# MCU_CAN.net
KiCad netlist of a schematic drawn in Altium Designer
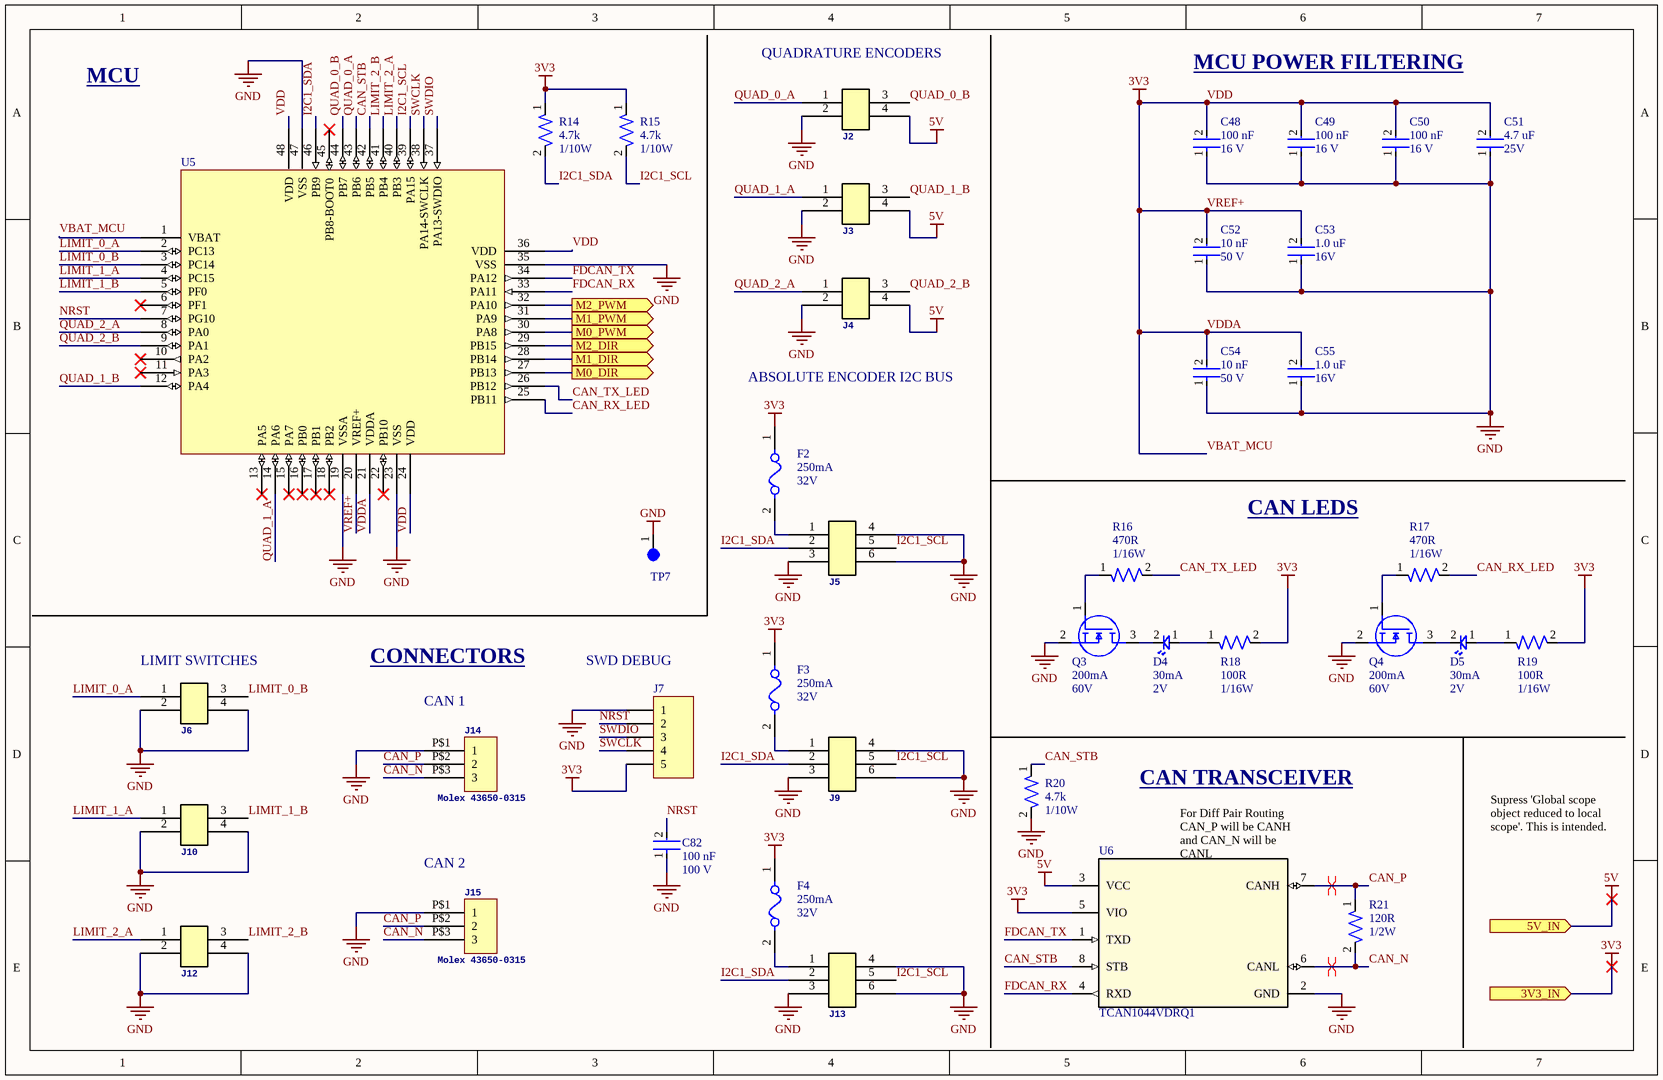
[diagram p0: MCU_CAN.SchDoc]

(export (version "E")
  (design (tool "Eeschema 10.0.6"))
  (components
    (comp (ref "C48")
      (value "CC0402KRX7R7BB104")
      (footprint "CAP-0402")
      (description "CAP CER 0.1UF 16V X7R 0402")
      (fields (field (name "VOLTAGE RATING") "16 V") (field (name "CAPACITANCE") "100 nF"))
      (libsource (lib "JLC_25") (part "CAP-0.1U-0001"))
    )
    (comp (ref "C49")
      (value "CC0402KRX7R7BB104")
      (footprint "CAP-0402")
      (description "CAP CER 0.1UF 16V X7R 0402")
      (fields (field (name "VOLTAGE RATING") "16 V") (field (name "CAPACITANCE") "100 nF"))
      (libsource (lib "JLC_25") (part "CAP-0.1U-0001"))
    )
    (comp (ref "C50")
      (value "CC0402KRX7R7BB104")
      (footprint "CAP-0402")
      (description "CAP CER 0.1UF 16V X7R 0402")
      (fields (field (name "VOLTAGE RATING") "16 V") (field (name "CAPACITANCE") "100 nF"))
      (libsource (lib "JLC_25") (part "CAP-0.1U-0001"))
    )
    (comp (ref "C51")
      (value "CC0603KRX5R8BB475")
      (footprint "CAP-0603")
      (description "CAP CER 4.7UF 25V X5R 0603")
      (fields (field (name "CAPACITANCE") "4.7 uF") (field (name "VOLTAGE") "25V"))
      (libsource (lib "JLC_25") (part "CAP-4.7U-0001"))
    )
    (comp (ref "C52")
      (value "CC0603KPX7R9BB103")
      (footprint "CAP-0603")
      (description "CAP CER 10000PF 50V X7R 0603")
      (fields (field (name "VOLTAGE") "50 V") (field (name "CAPACITANCE") "10 nF"))
      (libsource (lib "JLC_25") (part "CAP-10N-0002"))
    )
    (comp (ref "C53")
      (value "CC0603KRX7R7BB105")
      (footprint "CAP-0603")
      (description "CAP CER 1UF 16V X7R 0603")
      (fields (field (name "CAPACITANCE") "1.0 uF") (field (name "VOLTAGE") "16V"))
      (libsource (lib "JLC_25") (part "CAP-1U-0002"))
    )
    (comp (ref "C54")
      (value "CC0603KPX7R9BB103")
      (footprint "CAP-0603")
      (description "CAP CER 10000PF 50V X7R 0603")
      (fields (field (name "VOLTAGE") "50 V") (field (name "CAPACITANCE") "10 nF"))
      (libsource (lib "JLC_25") (part "CAP-10N-0002"))
    )
    (comp (ref "C55")
      (value "CC0603KRX7R7BB105")
      (footprint "CAP-0603")
      (description "CAP CER 1UF 16V X7R 0603")
      (fields (field (name "CAPACITANCE") "1.0 uF") (field (name "VOLTAGE") "16V"))
      (libsource (lib "JLC_25") (part "CAP-1U-0002"))
    )
    (comp (ref "C82")
      (value "CC0603KRX7R0BB104")
      (footprint "CAP-0603")
      (description "CAP CER 0.1UF 100V X7R 0603")
      (fields (field (name "CAPACITANCE") "100 nF") (field (name "VOLTAGE") "100 V"))
      (libsource (lib "JLC_25") (part "CAP-100N-0001"))
    )
    (comp (ref "D4")
      (value "BL-HKC36G-AV-TRB")
      (footprint "LED-0603")
      (description "LED YELLOW CLEAR 0603 SMD")
      (fields (field (name "FORWARD CURRENT") "30mA") (field (name "FORWARD VOLTAGE") "2V"))
      (libsource (lib "JLC_25") (part "LED-0001"))
    )
    (comp (ref "D5")
      (value "BL-HKC36G-AV-TRB")
      (footprint "LED-0603")
      (description "LED YELLOW CLEAR 0603 SMD")
      (fields (field (name "FORWARD CURRENT") "30mA") (field (name "FORWARD VOLTAGE") "2V"))
      (libsource (lib "JLC_25") (part "LED-0001"))
    )
    (comp (ref "F2")
      (value "0467.250NRHF")
      (footprint "RES-0603")
      (description "FUSE BRD MT 250MA 32VAC 32VDC")
      (fields (field (name "FUSE CURRENT") "250mA") (field (name "VOLTAGE RATING") "32V"))
      (libsource (lib "JLC_25") (part "FUSE-0002"))
    )
    (comp (ref "F3")
      (value "0467.250NRHF")
      (footprint "RES-0603")
      (description "FUSE BRD MT 250MA 32VAC 32VDC")
      (fields (field (name "FUSE CURRENT") "250mA") (field (name "VOLTAGE RATING") "32V"))
      (libsource (lib "JLC_25") (part "FUSE-0002"))
    )
    (comp (ref "F4")
      (value "0467.250NRHF")
      (footprint "RES-0603")
      (description "FUSE BRD MT 250MA 32VAC 32VDC")
      (fields (field (name "FUSE CURRENT") "250mA") (field (name "VOLTAGE RATING") "32V"))
      (libsource (lib "JLC_25") (part "FUSE-0002"))
    )
    (comp (ref "J2")
      (value "Molex 43045-0412")
      (footprint "CONN-4POS-0002")
      (description "CONN HEADER VERT 4POS 3MM")
      (libsource (lib "JLC_25") (part "CONN-4POS-0002"))
    )
    (comp (ref "J3")
      (value "Molex 43045-0412")
      (footprint "CONN-4POS-0002")
      (description "CONN HEADER VERT 4POS 3MM")
      (libsource (lib "JLC_25") (part "CONN-4POS-0002"))
    )
    (comp (ref "J4")
      (value "Molex 43045-0412")
      (footprint "CONN-4POS-0002")
      (description "CONN HEADER VERT 4POS 3MM")
      (libsource (lib "JLC_25") (part "CONN-4POS-0002"))
    )
    (comp (ref "J5")
      (value "Molex 43045-0612")
      (footprint "CONN-6POS-0001")
      (description "CONN HEADER VERT 6POS 3MM")
      (libsource (lib "JLC_25") (part "CONN-6POS-0001"))
    )
    (comp (ref "J6")
      (value "Molex 43045-0412")
      (footprint "CONN-4POS-0002")
      (description "CONN HEADER VERT 4POS 3MM")
      (libsource (lib "JLC_25") (part "CONN-4POS-0002"))
    )
    (comp (ref "J7")
      (value "Header 5")
      (footprint "HDR1X5")
      (description "Header, 5-Pin")
      (fields (field (name "PUBLISHER") "Altium Limited"))
      (libsource (lib "Miscellaneous Connectors") (part "Header 5"))
    )
    (comp (ref "J9")
      (value "Molex 43045-0612")
      (footprint "CONN-6POS-0001")
      (description "CONN HEADER VERT 6POS 3MM")
      (libsource (lib "JLC_25") (part "CONN-6POS-0001"))
    )
    (comp (ref "J10")
      (value "Molex 43045-0412")
      (footprint "CONN-4POS-0002")
      (description "CONN HEADER VERT 4POS 3MM")
      (libsource (lib "JLC_25") (part "CONN-4POS-0002"))
    )
    (comp (ref "J12")
      (value "Molex 43045-0412")
      (footprint "CONN-4POS-0002")
      (description "CONN HEADER VERT 4POS 3MM")
      (libsource (lib "JLC_25") (part "CONN-4POS-0002"))
    )
    (comp (ref "J13")
      (value "Molex 43045-0612")
      (footprint "CONN-6POS-0001")
      (description "CONN HEADER VERT 6POS 3MM")
      (libsource (lib "JLC_25") (part "CONN-6POS-0001"))
    )
    (comp (ref "J14")
      (value "Molex 43650-0315")
      (footprint "43650-0315")
      (libsource (lib "Molex Microfit") (part "Micro-Fit Molex 3 Pin Vertical"))
    )
    (comp (ref "J15")
      (value "Molex 43650-0315")
      (footprint "43650-0315")
      (libsource (lib "Molex Microfit") (part "Micro-Fit Molex 3 Pin Vertical"))
    )
    (comp (ref "Q3")
      (value "T2N7002AK,LM")
      (footprint "IC-SOT23-3")
      (description "MOSFET N-CH 60V 200MA SOT23")
      (fields (field (name "CONTINUOUS CURRENT") "200mA") (field (name "VOLTAGE") "60V"))
      (libsource (lib "JLC_25") (part "NMOS-200MA-0001"))
    )
    (comp (ref "Q4")
      (value "T2N7002AK,LM")
      (footprint "IC-SOT23-3")
      (description "MOSFET N-CH 60V 200MA SOT23")
      (fields (field (name "CONTINUOUS CURRENT") "200mA") (field (name "VOLTAGE") "60V"))
      (libsource (lib "JLC_25") (part "NMOS-200MA-0001"))
    )
    (comp (ref "R14")
      (value "RC0603FR-074K7L")
      (footprint "RES-0603")
      (description "RES 4.7K OHM 1% 1/10W 0603")
      (fields
        (field (name "TOLERANCE") "1%")
        (field (name "POWER") "1/10W")
        (field (name "RESISTANCE") "4.7k")
      )
      (libsource (lib "JLC_25") (part "RES-4.7k-0001"))
    )
    (comp (ref "R15")
      (value "RC0603FR-074K7L")
      (footprint "RES-0603")
      (description "RES 4.7K OHM 1% 1/10W 0603")
      (fields
        (field (name "TOLERANCE") "1%")
        (field (name "POWER") "1/10W")
        (field (name "RESISTANCE") "4.7k")
      )
      (libsource (lib "JLC_25") (part "RES-4.7k-0001"))
    )
    (comp (ref "R16")
      (value "RC0402FR-07470RL")
      (footprint "RES-0402")
      (description "RES 470 OHM 1% 1/16W 0402")
      (fields
        (field (name "TOLERANCE") "1%")
        (field (name "POWER") "1/16W")
        (field (name "RESISTANCE") "470R")
      )
      (libsource (lib "JLC_25") (part "RES-470-0001"))
    )
    (comp (ref "R17")
      (value "RC0402FR-07470RL")
      (footprint "RES-0402")
      (description "RES 470 OHM 1% 1/16W 0402")
      (fields
        (field (name "TOLERANCE") "1%")
        (field (name "POWER") "1/16W")
        (field (name "RESISTANCE") "470R")
      )
      (libsource (lib "JLC_25") (part "RES-470-0001"))
    )
    (comp (ref "R18")
      (value "RC0402FR-07100RL")
      (footprint "RES-0402")
      (description "RES 100 OHM 1% 1/16W 0402")
      (fields
        (field (name "TOLERANCE") "1%")
        (field (name "POWER") "1/16W")
        (field (name "RESISTANCE") "100R")
      )
      (libsource (lib "JLC_25") (part "RES-100-0001"))
    )
    (comp (ref "R19")
      (value "RC0402FR-07100RL")
      (footprint "RES-0402")
      (description "RES 100 OHM 1% 1/16W 0402")
      (fields
        (field (name "TOLERANCE") "1%")
        (field (name "POWER") "1/16W")
        (field (name "RESISTANCE") "100R")
      )
      (libsource (lib "JLC_25") (part "RES-100-0001"))
    )
    (comp (ref "R20")
      (value "RC0603FR-074K7L")
      (footprint "RES-0603")
      (description "RES 4.7K OHM 1% 1/10W 0603")
      (fields
        (field (name "TOLERANCE") "1%")
        (field (name "POWER") "1/10W")
        (field (name "RESISTANCE") "4.7k")
      )
      (libsource (lib "JLC_25") (part "RES-4.7k-0001"))
    )
    (comp (ref "R21")
      (value "RC1210FR-07120RL")
      (footprint "RES-1210")
      (description "RES 120 OHM 1% 1/2W 1210")
      (fields
        (field (name "TOLERANCE") "1%")
        (field (name "POWER") "1/2W")
        (field (name "RESISTANCE") "120R")
      )
      (libsource (lib "JLC_25") (part "RES-120-0001"))
    )
    (comp (ref "TP7")
      (value "5003")
      (footprint "TEST-POINT-0001")
      (description "Oranange PC Test Point, Miniature Phoisphor Bronze Silver Plating Through Hole Mounting Type")
      (libsource (lib "*") (part "TEST-POINT-0001"))
    )
    (comp (ref "U5")
      (value "STM32G431CBT6")
      (footprint "IC-LQFP48")
      (description "IC MCU 32BIT 128KB FLASH 48LQFP")
      (libsource (lib "JLC_25") (part "IC-STM32G431CBT6"))
    )
    (comp (ref "U6")
      (value "TCAN1044VDRQ1")
      (footprint "IC-8SOIC")
      (description "IC TRANSCEIVER 1/1 8SOIC")
      (libsource (lib "JLC_25") (part "IC-CAN-0001"))
    )
  )
  (nets
    (net (code "1") (name "/CAN_N") (class "Default")
      (node (ref "J14") (pin "P$3") (pinfunction "3_P$3") (pintype "passive"))
      (node (ref "J15") (pin "P$3") (pinfunction "3_P$3") (pintype "passive"))
      (node (ref "R21") (pin "2") (pinfunction "2_2") (pintype "passive"))
      (node (ref "U6") (pin "6") (pinfunction "CANL_6") (pintype "bidirectional"))
    )
    (net (code "2") (name "/CAN_P") (class "Default")
      (node (ref "J14") (pin "P$2") (pinfunction "2_P$2") (pintype "passive"))
      (node (ref "J15") (pin "P$2") (pinfunction "2_P$2") (pintype "passive"))
      (node (ref "R21") (pin "1") (pinfunction "1_1") (pintype "passive"))
      (node (ref "U6") (pin "7") (pinfunction "CANH_7") (pintype "bidirectional"))
    )
    (net (code "3") (name "/CAN_RX_LED") (class "Default")
      (node (ref "R17") (pin "2") (pinfunction "2_2") (pintype "passive"))
      (node (ref "U5") (pin "25") (pinfunction "PB11_25") (pintype "output"))
    )
    (net (code "4") (name "/CAN_STB") (class "Default")
      (node (ref "R20") (pin "1") (pinfunction "1_1") (pintype "passive"))
      (node (ref "U5") (pin "42") (pinfunction "PB5_42") (pintype "bidirectional"))
      (node (ref "U6") (pin "8") (pinfunction "STB_8") (pintype "input"))
    )
    (net (code "5") (name "/CAN_TX_LED") (class "Default")
      (node (ref "R16") (pin "2") (pinfunction "2_2") (pintype "passive"))
      (node (ref "U5") (pin "26") (pinfunction "PB12_26") (pintype "output"))
    )
    (net (code "6") (name "/FDCAN_RX") (class "Default")
      (node (ref "U5") (pin "33") (pinfunction "PA11_33") (pintype "input"))
      (node (ref "U6") (pin "4") (pinfunction "RXD_4") (pintype "output"))
    )
    (net (code "7") (name "/FDCAN_TX") (class "Default")
      (node (ref "U5") (pin "34") (pinfunction "PA12_34") (pintype "output"))
      (node (ref "U6") (pin "1") (pinfunction "TXD_1") (pintype "input"))
    )
    (net (code "8") (name "/I2C1_SCL") (class "Default")
      (node (ref "J13") (pin "5") (pinfunction "5_5") (pintype "passive"))
      (node (ref "J5") (pin "5") (pinfunction "5_5") (pintype "passive"))
      (node (ref "J9") (pin "5") (pinfunction "5_5") (pintype "passive"))
      (node (ref "R15") (pin "2") (pinfunction "2_2") (pintype "passive"))
      (node (ref "U5") (pin "39") (pinfunction "PA15_39") (pintype "bidirectional"))
    )
    (net (code "9") (name "/I2C1_SDA") (class "Default")
      (node (ref "J13") (pin "2") (pinfunction "2_2") (pintype "passive"))
      (node (ref "J5") (pin "2") (pinfunction "2_2") (pintype "passive"))
      (node (ref "J9") (pin "2") (pinfunction "2_2") (pintype "passive"))
      (node (ref "R14") (pin "2") (pinfunction "2_2") (pintype "passive"))
      (node (ref "U5") (pin "46") (pinfunction "PB9_46") (pintype "input"))
    )
    (net (code "10") (name "/LIMIT_0_A") (class "Default")
      (node (ref "J6") (pin "1") (pinfunction "1_1") (pintype "passive"))
      (node (ref "U5") (pin "2") (pinfunction "PC13_2") (pintype "bidirectional"))
    )
    (net (code "11") (name "/LIMIT_0_B") (class "Default")
      (node (ref "J6") (pin "3") (pinfunction "3_3") (pintype "passive"))
      (node (ref "U5") (pin "3") (pinfunction "PC14_3") (pintype "bidirectional"))
    )
    (net (code "12") (name "/LIMIT_1_A") (class "Default")
      (node (ref "J10") (pin "1") (pinfunction "1_1") (pintype "passive"))
      (node (ref "U5") (pin "4") (pinfunction "PC15_4") (pintype "bidirectional"))
    )
    (net (code "13") (name "/LIMIT_1_B") (class "Default")
      (node (ref "J10") (pin "3") (pinfunction "3_3") (pintype "passive"))
      (node (ref "U5") (pin "5") (pinfunction "PF0_5") (pintype "bidirectional"))
    )
    (net (code "14") (name "/LIMIT_2_A") (class "Default")
      (node (ref "J12") (pin "1") (pinfunction "1_1") (pintype "passive"))
      (node (ref "U5") (pin "40") (pinfunction "PB3_40") (pintype "bidirectional"))
    )
    (net (code "15") (name "/LIMIT_2_B") (class "Default")
      (node (ref "J12") (pin "3") (pinfunction "3_3") (pintype "passive"))
      (node (ref "U5") (pin "41") (pinfunction "PB4_41") (pintype "bidirectional"))
    )
    (net (code "16") (name "/M0_DIR") (class "Default")
      (node (ref "U5") (pin "27") (pinfunction "PB13_27") (pintype "output"))
    )
    (net (code "17") (name "/M0_PWM") (class "Default")
      (node (ref "U5") (pin "30") (pinfunction "PA8_30") (pintype "output"))
    )
    (net (code "18") (name "/M1_DIR") (class "Default")
      (node (ref "U5") (pin "28") (pinfunction "PB14_28") (pintype "output"))
    )
    (net (code "19") (name "/M1_PWM") (class "Default")
      (node (ref "U5") (pin "31") (pinfunction "PA9_31") (pintype "output"))
    )
    (net (code "20") (name "/M2_DIR") (class "Default")
      (node (ref "U5") (pin "29") (pinfunction "PB15_29") (pintype "output"))
    )
    (net (code "21") (name "/M2_PWM") (class "Default")
      (node (ref "U5") (pin "32") (pinfunction "PA10_32") (pintype "output"))
    )
    (net (code "22") (name "/NRST") (class "Default")
      (node (ref "C82") (pin "2") (pinfunction "2_2") (pintype "passive"))
      (node (ref "J7") (pin "2") (pinfunction "2_2") (pintype "passive"))
      (node (ref "U5") (pin "7") (pinfunction "PG10_7") (pintype "bidirectional"))
    )
    (net (code "23") (name "/QUAD_0_A") (class "Default")
      (node (ref "J2") (pin "1") (pinfunction "1_1") (pintype "passive"))
      (node (ref "U5") (pin "43") (pinfunction "PB6_43") (pintype "bidirectional"))
    )
    (net (code "24") (name "/QUAD_0_B") (class "Default")
      (node (ref "J2") (pin "3") (pinfunction "3_3") (pintype "passive"))
      (node (ref "U5") (pin "44") (pinfunction "PB7_44") (pintype "bidirectional"))
    )
    (net (code "25") (name "/QUAD_1_A") (class "Default")
      (node (ref "J3") (pin "1") (pinfunction "1_1") (pintype "passive"))
      (node (ref "U5") (pin "14") (pinfunction "PA6_14") (pintype "bidirectional"))
    )
    (net (code "26") (name "/QUAD_1_B") (class "Default")
      (node (ref "J3") (pin "3") (pinfunction "3_3") (pintype "passive"))
      (node (ref "U5") (pin "12") (pinfunction "PA4_12") (pintype "bidirectional"))
    )
    (net (code "27") (name "/QUAD_2_A") (class "Default")
      (node (ref "J4") (pin "1") (pinfunction "1_1") (pintype "passive"))
      (node (ref "U5") (pin "8") (pinfunction "PA0_8") (pintype "bidirectional"))
    )
    (net (code "28") (name "/QUAD_2_B") (class "Default")
      (node (ref "J4") (pin "3") (pinfunction "3_3") (pintype "passive"))
      (node (ref "U5") (pin "9") (pinfunction "PA1_9") (pintype "bidirectional"))
    )
    (net (code "29") (name "/SWCLK") (class "Default")
      (node (ref "J7") (pin "4") (pinfunction "4_4") (pintype "passive"))
      (node (ref "U5") (pin "38") (pinfunction "PA14-SWCLK_38") (pintype "input"))
    )
    (net (code "30") (name "/SWDIO") (class "Default")
      (node (ref "J7") (pin "3") (pinfunction "3_3") (pintype "passive"))
      (node (ref "U5") (pin "37") (pinfunction "PA13-SWDIO_37") (pintype "input"))
    )
    (net (code "31") (name "3V3") (class "Default")
      (node (ref "C48") (pin "2") (pinfunction "2_2") (pintype "passive"))
      (node (ref "C49") (pin "2") (pinfunction "2_2") (pintype "passive"))
      (node (ref "C50") (pin "2") (pinfunction "2_2") (pintype "passive"))
      (node (ref "C51") (pin "2") (pinfunction "2_2") (pintype "passive"))
      (node (ref "C52") (pin "2") (pinfunction "2_2") (pintype "passive"))
      (node (ref "C53") (pin "2") (pinfunction "2_2") (pintype "passive"))
      (node (ref "C54") (pin "2") (pinfunction "2_2") (pintype "passive"))
      (node (ref "C55") (pin "2") (pinfunction "2_2") (pintype "passive"))
      (node (ref "F2") (pin "1") (pinfunction "1_1") (pintype "passive"))
      (node (ref "F3") (pin "1") (pinfunction "1_1") (pintype "passive"))
      (node (ref "F4") (pin "1") (pinfunction "1_1") (pintype "passive"))
      (node (ref "J7") (pin "5") (pinfunction "5_5") (pintype "passive"))
      (node (ref "R14") (pin "1") (pinfunction "1_1") (pintype "passive"))
      (node (ref "R15") (pin "1") (pinfunction "1_1") (pintype "passive"))
      (node (ref "R18") (pin "2") (pinfunction "2_2") (pintype "passive"))
      (node (ref "R19") (pin "2") (pinfunction "2_2") (pintype "passive"))
      (node (ref "U5") (pin "1") (pinfunction "VBAT_1") (pintype "power_in"))
      (node (ref "U5") (pin "20") (pinfunction "VREF+_20") (pintype "power_in"))
      (node (ref "U5") (pin "21") (pinfunction "VDDA_21") (pintype "power_in"))
      (node (ref "U5") (pin "24") (pinfunction "VDD_24") (pintype "power_in"))
      (node (ref "U5") (pin "36") (pinfunction "VDD_36") (pintype "power_in"))
      (node (ref "U5") (pin "48") (pinfunction "VDD_48") (pintype "power_in"))
      (node (ref "U6") (pin "5") (pinfunction "VIO_5") (pintype "power_in"))
    )
    (net (code "32") (name "5V") (class "Default")
      (node (ref "J2") (pin "4") (pinfunction "4_4") (pintype "passive"))
      (node (ref "J3") (pin "4") (pinfunction "4_4") (pintype "passive"))
      (node (ref "J4") (pin "4") (pinfunction "4_4") (pintype "passive"))
      (node (ref "U6") (pin "3") (pinfunction "VCC_3") (pintype "power_in"))
    )
    (net (code "33") (name "GND") (class "Default")
      (node (ref "C48") (pin "1") (pinfunction "1_1") (pintype "passive"))
      (node (ref "C49") (pin "1") (pinfunction "1_1") (pintype "passive"))
      (node (ref "C50") (pin "1") (pinfunction "1_1") (pintype "passive"))
      (node (ref "C51") (pin "1") (pinfunction "1_1") (pintype "passive"))
      (node (ref "C52") (pin "1") (pinfunction "1_1") (pintype "passive"))
      (node (ref "C53") (pin "1") (pinfunction "1_1") (pintype "passive"))
      (node (ref "C54") (pin "1") (pinfunction "1_1") (pintype "passive"))
      (node (ref "C55") (pin "1") (pinfunction "1_1") (pintype "passive"))
      (node (ref "C82") (pin "1") (pinfunction "1_1") (pintype "passive"))
      (node (ref "J10") (pin "2") (pinfunction "2_2") (pintype "passive"))
      (node (ref "J10") (pin "4") (pinfunction "4_4") (pintype "passive"))
      (node (ref "J12") (pin "2") (pinfunction "2_2") (pintype "passive"))
      (node (ref "J12") (pin "4") (pinfunction "4_4") (pintype "passive"))
      (node (ref "J13") (pin "3") (pinfunction "3_3") (pintype "passive"))
      (node (ref "J13") (pin "4") (pinfunction "4_4") (pintype "passive"))
      (node (ref "J13") (pin "6") (pinfunction "6_6") (pintype "passive"))
      (node (ref "J14") (pin "P$1") (pinfunction "1_P$1") (pintype "passive"))
      (node (ref "J15") (pin "P$1") (pinfunction "1_P$1") (pintype "passive"))
      (node (ref "J2") (pin "2") (pinfunction "2_2") (pintype "passive"))
      (node (ref "J3") (pin "2") (pinfunction "2_2") (pintype "passive"))
      (node (ref "J4") (pin "2") (pinfunction "2_2") (pintype "passive"))
      (node (ref "J5") (pin "3") (pinfunction "3_3") (pintype "passive"))
      (node (ref "J5") (pin "4") (pinfunction "4_4") (pintype "passive"))
      (node (ref "J5") (pin "6") (pinfunction "6_6") (pintype "passive"))
      (node (ref "J6") (pin "2") (pinfunction "2_2") (pintype "passive"))
      (node (ref "J6") (pin "4") (pinfunction "4_4") (pintype "passive"))
      (node (ref "J7") (pin "1") (pinfunction "1_1") (pintype "passive"))
      (node (ref "J9") (pin "3") (pinfunction "3_3") (pintype "passive"))
      (node (ref "J9") (pin "4") (pinfunction "4_4") (pintype "passive"))
      (node (ref "J9") (pin "6") (pinfunction "6_6") (pintype "passive"))
      (node (ref "Q3") (pin "2") (pinfunction "S_2") (pintype "passive"))
      (node (ref "Q4") (pin "2") (pinfunction "S_2") (pintype "passive"))
      (node (ref "R20") (pin "2") (pinfunction "2_2") (pintype "passive"))
      (node (ref "TP7") (pin "1") (pinfunction "0_1") (pintype "passive"))
      (node (ref "U5") (pin "19") (pinfunction "VSSA_19") (pintype "power_in"))
      (node (ref "U5") (pin "23") (pinfunction "VSS_23") (pintype "power_in"))
      (node (ref "U5") (pin "35") (pinfunction "VSS_35") (pintype "power_in"))
      (node (ref "U5") (pin "47") (pinfunction "VSS_47") (pintype "power_in"))
      (node (ref "U6") (pin "2") (pinfunction "GND_2") (pintype "power_in"))
    )
    (net (code "34") (name "Net-(D4-Pad1)") (class "Default")
      (node (ref "D4") (pin "1") (pinfunction "1_1") (pintype "passive"))
      (node (ref "R18") (pin "1") (pinfunction "1_1") (pintype "passive"))
    )
    (net (code "35") (name "Net-(D5-Pad1)") (class "Default")
      (node (ref "D5") (pin "1") (pinfunction "1_1") (pintype "passive"))
      (node (ref "R19") (pin "1") (pinfunction "1_1") (pintype "passive"))
    )
    (net (code "36") (name "Net-(J5-7)") (class "Default")
      (node (ref "F2") (pin "2") (pinfunction "2_2") (pintype "passive"))
      (node (ref "J5") (pin "1") (pinfunction "7_1") (pintype "passive"))
    )
    (net (code "37") (name "Net-(J9-7)") (class "Default")
      (node (ref "F3") (pin "2") (pinfunction "2_2") (pintype "passive"))
      (node (ref "J9") (pin "1") (pinfunction "7_1") (pintype "passive"))
    )
    (net (code "38") (name "Net-(J13-7)") (class "Default")
      (node (ref "F4") (pin "2") (pinfunction "2_2") (pintype "passive"))
      (node (ref "J13") (pin "1") (pinfunction "7_1") (pintype "passive"))
    )
    (net (code "39") (name "Net-(Q3-D)") (class "Default")
      (node (ref "D4") (pin "2") (pinfunction "2_2") (pintype "passive"))
      (node (ref "Q3") (pin "3") (pinfunction "D_3") (pintype "passive"))
    )
    (net (code "40") (name "Net-(Q3-G)") (class "Default")
      (node (ref "Q3") (pin "1") (pinfunction "G_1") (pintype "passive"))
      (node (ref "R16") (pin "1") (pinfunction "1_1") (pintype "passive"))
    )
    (net (code "41") (name "Net-(Q4-D)") (class "Default")
      (node (ref "D5") (pin "2") (pinfunction "2_2") (pintype "passive"))
      (node (ref "Q4") (pin "3") (pinfunction "D_3") (pintype "passive"))
    )
    (net (code "42") (name "Net-(Q4-G)") (class "Default")
      (node (ref "Q4") (pin "1") (pinfunction "G_1") (pintype "passive"))
      (node (ref "R17") (pin "1") (pinfunction "1_1") (pintype "passive"))
    )
    (net (code "43") (name "unconnected-(U5-PA2-Pad10)") (class "Default")
      (node (ref "U5") (pin "10") (pinfunction "PA2_10") (pintype "output+no_connect"))
    )
    (net (code "44") (name "unconnected-(U5-PA3-Pad11)") (class "Default")
      (node (ref "U5") (pin "11") (pinfunction "PA3_11") (pintype "input+no_connect"))
    )
    (net (code "45") (name "unconnected-(U5-PA5-Pad13)") (class "Default")
      (node (ref "U5") (pin "13") (pinfunction "PA5_13") (pintype "bidirectional+no_connect"))
    )
    (net (code "46") (name "unconnected-(U5-PA7-Pad15)") (class "Default")
      (node (ref "U5") (pin "15") (pinfunction "PA7_15") (pintype "bidirectional+no_connect"))
    )
    (net (code "47") (name "unconnected-(U5-PB0-Pad16)") (class "Default")
      (node (ref "U5") (pin "16") (pinfunction "PB0_16") (pintype "bidirectional+no_connect"))
    )
    (net (code "48") (name "unconnected-(U5-PB1-Pad17)") (class "Default")
      (node (ref "U5") (pin "17") (pinfunction "PB1_17") (pintype "bidirectional+no_connect"))
    )
    (net (code "49") (name "unconnected-(U5-PB2-Pad18)") (class "Default")
      (node (ref "U5") (pin "18") (pinfunction "PB2_18") (pintype "bidirectional+no_connect"))
    )
    (net (code "50") (name "unconnected-(U5-PB8-BOOT0-Pad45)") (class "Default")
      (node (ref "U5") (pin "45") (pinfunction "PB8-BOOT0_45") (pintype "bidirectional+no_connect"))
    )
    (net (code "51") (name "unconnected-(U5-PB10-Pad22)") (class "Default")
      (node (ref "U5") (pin "22") (pinfunction "PB10_22") (pintype "bidirectional+no_connect"))
    )
    (net (code "52") (name "unconnected-(U5-PF1-Pad6)") (class "Default")
      (node (ref "U5") (pin "6") (pinfunction "PF1_6") (pintype "bidirectional+no_connect"))
    )
  )
)
